# Error_Schematic.net
KiCad netlist of a schematic drawn in Altium Designer
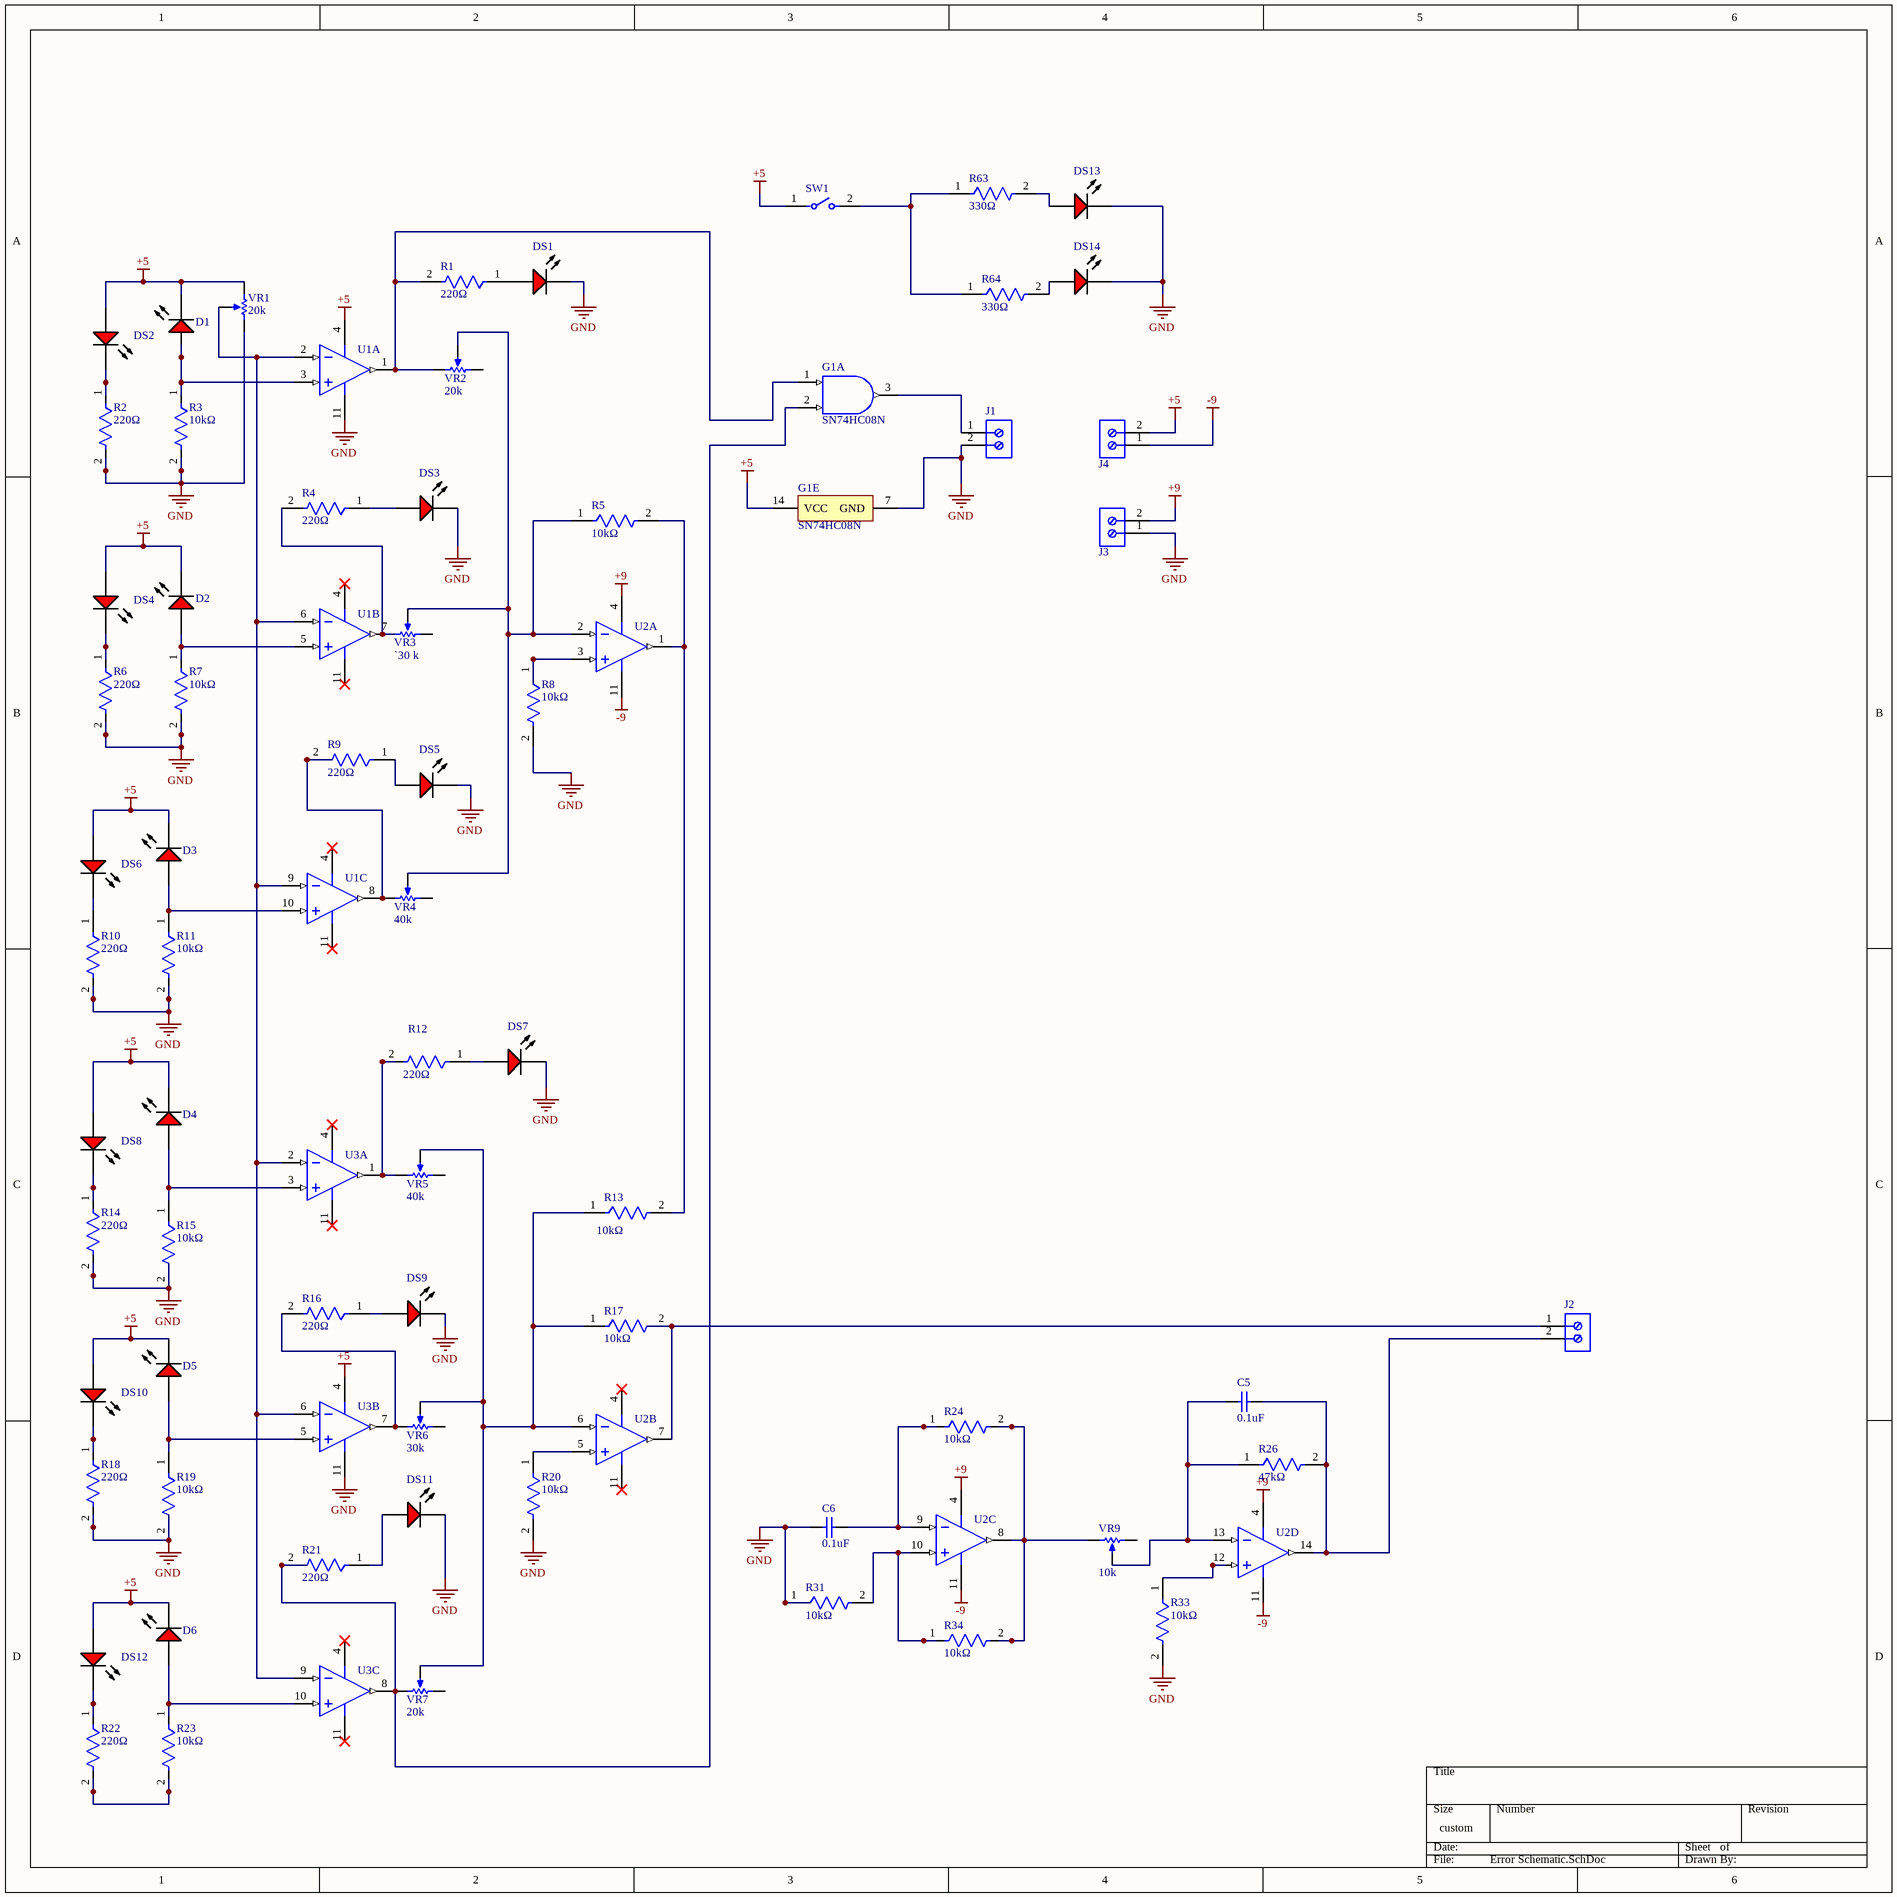
[diagram p0: Error Schematic.SchDoc]

(export (version "E")
  (design (tool "Eeschema 10.0.6"))
  (components
    (comp (ref "C5")
      (value "0.1uF")
      (footprint "CAPR51-254-508X318X736")
      (fields (field (name "Comment") "C320C104K5R5TA"))
      (libsource (lib "Altium Content Vault") (part "CAP-NP-2"))
    )
    (comp (ref "C6")
      (value "0.1uF")
      (footprint "CAPR51-254-508X318X736")
      (fields (field (name "Comment") "C320C104K5R5TA"))
      (libsource (lib "Altium Content Vault") (part "CAP-NP-2"))
    )
    (comp (ref "D1")
      (value "HLMP-3301")
      (footprint "AVAG-HLMP-3301-2")
      (description "T-1 3/4 (5 mm) Diffused LED Lamp, 1.9 V, -40 to 100 degC, 2-Pin THD, RoHS, Bulk")
      (fields (field (name "MANUFACTURER") "Avago"))
      (libsource (lib "Altium Content Vault") (part "LED-RED-K1A2-2"))
    )
    (comp (ref "D2")
      (value "HLMP-3301")
      (footprint "AVAG-HLMP-3301-2")
      (description "T-1 3/4 (5 mm) Diffused LED Lamp, 1.9 V, -40 to 100 degC, 2-Pin THD, RoHS, Bulk")
      (fields (field (name "MANUFACTURER") "Avago"))
      (libsource (lib "Altium Content Vault") (part "LED-RED-K1A2-2"))
    )
    (comp (ref "D3")
      (value "HLMP-3301")
      (footprint "AVAG-HLMP-3301-2")
      (description "T-1 3/4 (5 mm) Diffused LED Lamp, 1.9 V, -40 to 100 degC, 2-Pin THD, RoHS, Bulk")
      (fields (field (name "MANUFACTURER") "Avago"))
      (libsource (lib "Altium Content Vault") (part "LED-RED-K1A2-2"))
    )
    (comp (ref "D4")
      (value "HLMP-3301")
      (footprint "AVAG-HLMP-3301-2")
      (description "T-1 3/4 (5 mm) Diffused LED Lamp, 1.9 V, -40 to 100 degC, 2-Pin THD, RoHS, Bulk")
      (fields (field (name "MANUFACTURER") "Avago"))
      (libsource (lib "Altium Content Vault") (part "LED-RED-K1A2-2"))
    )
    (comp (ref "D5")
      (value "HLMP-3301")
      (footprint "AVAG-HLMP-3301-2")
      (description "T-1 3/4 (5 mm) Diffused LED Lamp, 1.9 V, -40 to 100 degC, 2-Pin THD, RoHS, Bulk")
      (fields (field (name "MANUFACTURER") "Avago"))
      (libsource (lib "Altium Content Vault") (part "LED-RED-K1A2-2"))
    )
    (comp (ref "D6")
      (value "HLMP-3301")
      (footprint "AVAG-HLMP-3301-2")
      (description "T-1 3/4 (5 mm) Diffused LED Lamp, 1.9 V, -40 to 100 degC, 2-Pin THD, RoHS, Bulk")
      (fields (field (name "MANUFACTURER") "Avago"))
      (libsource (lib "Altium Content Vault") (part "LED-RED-K1A2-2"))
    )
    (comp (ref "DS1")
      (value "HLMP-3301")
      (footprint "AVAG-HLMP-3301-2")
      (description "T-1 3/4 (5 mm) Diffused LED Lamp, 1.9 V, -40 to 100 degC, 2-Pin THD, RoHS, Bulk")
      (fields (field (name "MANUFACTURER") "Avago"))
      (libsource (lib "Altium Content Vault") (part "LED-RED-K1A2-2"))
    )
    (comp (ref "DS2")
      (value "HLMP-3301")
      (footprint "AVAG-HLMP-3301-2")
      (description "T-1 3/4 (5 mm) Diffused LED Lamp, 1.9 V, -40 to 100 degC, 2-Pin THD, RoHS, Bulk")
      (fields (field (name "MANUFACTURER") "Avago"))
      (libsource (lib "Altium Content Vault") (part "LED-RED-K1A2-2"))
    )
    (comp (ref "DS3")
      (value "HLMP-3301")
      (footprint "AVAG-HLMP-3301-2")
      (description "T-1 3/4 (5 mm) Diffused LED Lamp, 1.9 V, -40 to 100 degC, 2-Pin THD, RoHS, Bulk")
      (fields (field (name "MANUFACTURER") "Avago"))
      (libsource (lib "Altium Content Vault") (part "LED-RED-K1A2-2"))
    )
    (comp (ref "DS4")
      (value "HLMP-3301")
      (footprint "AVAG-HLMP-3301-2")
      (description "T-1 3/4 (5 mm) Diffused LED Lamp, 1.9 V, -40 to 100 degC, 2-Pin THD, RoHS, Bulk")
      (fields (field (name "MANUFACTURER") "Avago"))
      (libsource (lib "Altium Content Vault") (part "LED-RED-K1A2-2"))
    )
    (comp (ref "DS5")
      (value "HLMP-3301")
      (footprint "AVAG-HLMP-3301-2")
      (description "T-1 3/4 (5 mm) Diffused LED Lamp, 1.9 V, -40 to 100 degC, 2-Pin THD, RoHS, Bulk")
      (fields (field (name "MANUFACTURER") "Avago"))
      (libsource (lib "Altium Content Vault") (part "LED-RED-K1A2-2"))
    )
    (comp (ref "DS6")
      (value "HLMP-3301")
      (footprint "AVAG-HLMP-3301-2")
      (description "T-1 3/4 (5 mm) Diffused LED Lamp, 1.9 V, -40 to 100 degC, 2-Pin THD, RoHS, Bulk")
      (fields (field (name "MANUFACTURER") "Avago"))
      (libsource (lib "Altium Content Vault") (part "LED-RED-K1A2-2"))
    )
    (comp (ref "DS7")
      (value "HLMP-3301")
      (footprint "AVAG-HLMP-3301-2")
      (description "T-1 3/4 (5 mm) Diffused LED Lamp, 1.9 V, -40 to 100 degC, 2-Pin THD, RoHS, Bulk")
      (fields (field (name "MANUFACTURER") "Avago"))
      (libsource (lib "Altium Content Vault") (part "LED-RED-K1A2-2"))
    )
    (comp (ref "DS8")
      (value "HLMP-3301")
      (footprint "AVAG-HLMP-3301-2")
      (description "T-1 3/4 (5 mm) Diffused LED Lamp, 1.9 V, -40 to 100 degC, 2-Pin THD, RoHS, Bulk")
      (fields (field (name "MANUFACTURER") "Avago"))
      (libsource (lib "Altium Content Vault") (part "LED-RED-K1A2-2"))
    )
    (comp (ref "DS9")
      (value "HLMP-3301")
      (footprint "AVAG-HLMP-3301-2")
      (description "T-1 3/4 (5 mm) Diffused LED Lamp, 1.9 V, -40 to 100 degC, 2-Pin THD, RoHS, Bulk")
      (fields (field (name "MANUFACTURER") "Avago"))
      (libsource (lib "Altium Content Vault") (part "LED-RED-K1A2-2"))
    )
    (comp (ref "DS10")
      (value "HLMP-3301")
      (footprint "AVAG-HLMP-3301-2")
      (description "T-1 3/4 (5 mm) Diffused LED Lamp, 1.9 V, -40 to 100 degC, 2-Pin THD, RoHS, Bulk")
      (fields (field (name "MANUFACTURER") "Avago"))
      (libsource (lib "Altium Content Vault") (part "LED-RED-K1A2-2"))
    )
    (comp (ref "DS11")
      (value "HLMP-3301")
      (footprint "AVAG-HLMP-3301-2")
      (description "T-1 3/4 (5 mm) Diffused LED Lamp, 1.9 V, -40 to 100 degC, 2-Pin THD, RoHS, Bulk")
      (fields (field (name "MANUFACTURER") "Avago"))
      (libsource (lib "Altium Content Vault") (part "LED-RED-K1A2-2"))
    )
    (comp (ref "DS12")
      (value "HLMP-3301")
      (footprint "AVAG-HLMP-3301-2")
      (description "T-1 3/4 (5 mm) Diffused LED Lamp, 1.9 V, -40 to 100 degC, 2-Pin THD, RoHS, Bulk")
      (fields (field (name "MANUFACTURER") "Avago"))
      (libsource (lib "Altium Content Vault") (part "LED-RED-K1A2-2"))
    )
    (comp (ref "DS13")
      (value "HLMP-3301")
      (footprint "AVAG-HLMP-3301-2")
      (description "T-1 3/4 (5 mm) Diffused LED Lamp, 1.9 V, -40 to 100 degC, 2-Pin THD, RoHS, Bulk")
      (fields (field (name "MANUFACTURER") "Avago"))
      (libsource (lib "Altium Content Vault") (part "LED-RED-K1A2-2"))
    )
    (comp (ref "DS14")
      (value "HLMP-3301")
      (footprint "AVAG-HLMP-3301-2")
      (description "T-1 3/4 (5 mm) Diffused LED Lamp, 1.9 V, -40 to 100 degC, 2-Pin THD, RoHS, Bulk")
      (fields (field (name "MANUFACTURER") "Avago"))
      (libsource (lib "Altium Content Vault") (part "LED-RED-K1A2-2"))
    )
    (comp (ref "G1")
      (value "SN74HC08N")
      (footprint "N0014A")
      (description "Quadruple 2-Input Positive-AND Gates, N0014A, TUBE")
      (fields
        (field (name "GENERIC PART NUMBER") "SN74HC08")
        (field (name "MANUFACTURER") "Texas Instruments")
      )
      (libsource (lib "Altium Content Vault") (part "TI-AND-4-2IN-14"))
    )
    (comp (ref "J1")
      (value "691103110002")
      (footprint "691103110002")
      (description "Series 1031 - 3.50 mm Horizontal Entry Modular with Pressure Clamp WR-TBL, 2 pin")
      (fields (field (name "MANUFACTURER") "Wurth Elektronik") (field (name "PUBLISHER") "WurthElektronik"))
      (libsource (lib "Altium Content Vault") (part "WE-CN-1P-F-TB2"))
    )
    (comp (ref "J2")
      (value "691103110002")
      (footprint "691103110002")
      (description "Series 1031 - 3.50 mm Horizontal Entry Modular with Pressure Clamp WR-TBL, 2 pin")
      (fields (field (name "MANUFACTURER") "Wurth Elektronik") (field (name "PUBLISHER") "WurthElektronik"))
      (libsource (lib "Altium Content Vault") (part "WE-CN-1P-F-TB2"))
    )
    (comp (ref "J3")
      (value "691103110002")
      (footprint "691103110002")
      (description "Series 1031 - 3.50 mm Horizontal Entry Modular with Pressure Clamp WR-TBL, 2 pin")
      (fields (field (name "MANUFACTURER") "Wurth Elektronik") (field (name "PUBLISHER") "WurthElektronik"))
      (libsource (lib "Altium Content Vault") (part "WE-CN-1P-F-TB2"))
    )
    (comp (ref "J4")
      (value "691103110002")
      (footprint "691103110002")
      (description "Series 1031 - 3.50 mm Horizontal Entry Modular with Pressure Clamp WR-TBL, 2 pin")
      (fields (field (name "MANUFACTURER") "Wurth Elektronik") (field (name "PUBLISHER") "WurthElektronik"))
      (libsource (lib "Altium Content Vault") (part "WE-CN-1P-F-TB2"))
    )
    (comp (ref "R1")
      (value "MRS25000C1101FCT00")
      (footprint "FP-MRS25-MFG")
      (description "RES 1.1K OHM 0.6W 1% AXIAL")
      (fields
        (field (name "MANUFACTURER") "Vishay BC Components")
        (field (name "OCTOPART") "https://octopart.com/mrs25000c1101fct00-vishay-43740214")
        (field (name "RESISTANCE") "220Ω")
      )
      (libsource (lib "Altium Content Vault") (part "1029c3af85768c4190bb7ad29bc67b5"))
    )
    (comp (ref "R2")
      (value "MRS25000C1101FCT00")
      (footprint "FP-MRS25-MFG")
      (description "RES 1.1K OHM 0.6W 1% AXIAL")
      (fields
        (field (name "MANUFACTURER") "Vishay BC Components")
        (field (name "OCTOPART") "https://octopart.com/mrs25000c1101fct00-vishay-43740214")
        (field (name "RESISTANCE") "220Ω")
      )
      (libsource (lib "Altium Content Vault") (part "1029c3af85768c4190bb7ad29bc67b5"))
    )
    (comp (ref "R3")
      (value "MRS25000C1101FCT00")
      (footprint "FP-MRS25-MFG")
      (description "RES 1.1K OHM 0.6W 1% AXIAL")
      (fields
        (field (name "MANUFACTURER") "Vishay BC Components")
        (field (name "OCTOPART") "https://octopart.com/mrs25000c1101fct00-vishay-43740214")
        (field (name "RESISTANCE") "10kΩ")
      )
      (libsource (lib "Altium Content Vault") (part "1029c3af85768c4190bb7ad29bc67b5"))
    )
    (comp (ref "R4")
      (value "MRS25000C1101FCT00")
      (footprint "FP-MRS25-MFG")
      (description "RES 1.1K OHM 0.6W 1% AXIAL")
      (fields
        (field (name "MANUFACTURER") "Vishay BC Components")
        (field (name "OCTOPART") "https://octopart.com/mrs25000c1101fct00-vishay-43740214")
        (field (name "RESISTANCE") "220Ω")
      )
      (libsource (lib "Altium Content Vault") (part "1029c3af85768c4190bb7ad29bc67b5"))
    )
    (comp (ref "R5")
      (value "MRS25000C1101FCT00")
      (footprint "FP-MRS25-MFG")
      (description "RES 1.1K OHM 0.6W 1% AXIAL")
      (fields
        (field (name "MANUFACTURER") "Vishay BC Components")
        (field (name "OCTOPART") "https://octopart.com/mrs25000c1101fct00-vishay-43740214")
        (field (name "RESISTANCE") "10kΩ")
      )
      (libsource (lib "Altium Content Vault") (part "1029c3af85768c4190bb7ad29bc67b5"))
    )
    (comp (ref "R6")
      (value "MRS25000C1101FCT00")
      (footprint "FP-MRS25-MFG")
      (description "RES 1.1K OHM 0.6W 1% AXIAL")
      (fields
        (field (name "MANUFACTURER") "Vishay BC Components")
        (field (name "OCTOPART") "https://octopart.com/mrs25000c1101fct00-vishay-43740214")
        (field (name "RESISTANCE") "220Ω")
      )
      (libsource (lib "Altium Content Vault") (part "1029c3af85768c4190bb7ad29bc67b5"))
    )
    (comp (ref "R7")
      (value "MRS25000C1101FCT00")
      (footprint "FP-MRS25-MFG")
      (description "RES 1.1K OHM 0.6W 1% AXIAL")
      (fields
        (field (name "MANUFACTURER") "Vishay BC Components")
        (field (name "OCTOPART") "https://octopart.com/mrs25000c1101fct00-vishay-43740214")
        (field (name "RESISTANCE") "10kΩ")
      )
      (libsource (lib "Altium Content Vault") (part "1029c3af85768c4190bb7ad29bc67b5"))
    )
    (comp (ref "R8")
      (value "MRS25000C1101FCT00")
      (footprint "FP-MRS25-MFG")
      (description "RES 1.1K OHM 0.6W 1% AXIAL")
      (fields
        (field (name "MANUFACTURER") "Vishay BC Components")
        (field (name "OCTOPART") "https://octopart.com/mrs25000c1101fct00-vishay-43740214")
        (field (name "RESISTANCE") "10kΩ")
      )
      (libsource (lib "Altium Content Vault") (part "1029c3af85768c4190bb7ad29bc67b5"))
    )
    (comp (ref "R9")
      (value "MRS25000C1101FCT00")
      (footprint "FP-MRS25-MFG")
      (description "RES 1.1K OHM 0.6W 1% AXIAL")
      (fields
        (field (name "MANUFACTURER") "Vishay BC Components")
        (field (name "OCTOPART") "https://octopart.com/mrs25000c1101fct00-vishay-43740214")
        (field (name "RESISTANCE") "220Ω")
      )
      (libsource (lib "Altium Content Vault") (part "1029c3af85768c4190bb7ad29bc67b5"))
    )
    (comp (ref "R10")
      (value "MRS25000C1101FCT00")
      (footprint "FP-MRS25-MFG")
      (description "RES 1.1K OHM 0.6W 1% AXIAL")
      (fields
        (field (name "MANUFACTURER") "Vishay BC Components")
        (field (name "OCTOPART") "https://octopart.com/mrs25000c1101fct00-vishay-43740214")
        (field (name "RESISTANCE") "220Ω")
      )
      (libsource (lib "Altium Content Vault") (part "1029c3af85768c4190bb7ad29bc67b5"))
    )
    (comp (ref "R11")
      (value "MRS25000C1101FCT00")
      (footprint "FP-MRS25-MFG")
      (description "RES 1.1K OHM 0.6W 1% AXIAL")
      (fields
        (field (name "MANUFACTURER") "Vishay BC Components")
        (field (name "OCTOPART") "https://octopart.com/mrs25000c1101fct00-vishay-43740214")
        (field (name "RESISTANCE") "10kΩ")
      )
      (libsource (lib "Altium Content Vault") (part "1029c3af85768c4190bb7ad29bc67b5"))
    )
    (comp (ref "R12")
      (value "MRS25000C1101FCT00")
      (footprint "FP-MRS25-MFG")
      (description "RES 1.1K OHM 0.6W 1% AXIAL")
      (fields
        (field (name "MANUFACTURER") "Vishay BC Components")
        (field (name "OCTOPART") "https://octopart.com/mrs25000c1101fct00-vishay-43740214")
        (field (name "RESISTANCE") "220Ω")
      )
      (libsource (lib "Altium Content Vault") (part "1029c3af85768c4190bb7ad29bc67b5"))
    )
    (comp (ref "R13")
      (value "MRS25000C1101FCT00")
      (footprint "FP-MRS25-MFG")
      (description "RES 1.1K OHM 0.6W 1% AXIAL")
      (fields
        (field (name "MANUFACTURER") "Vishay BC Components")
        (field (name "OCTOPART") "https://octopart.com/mrs25000c1101fct00-vishay-43740214")
        (field (name "RESISTANCE") "10kΩ")
      )
      (libsource (lib "Altium Content Vault") (part "1029c3af85768c4190bb7ad29bc67b5"))
    )
    (comp (ref "R14")
      (value "MRS25000C1101FCT00")
      (footprint "FP-MRS25-MFG")
      (description "RES 1.1K OHM 0.6W 1% AXIAL")
      (fields
        (field (name "MANUFACTURER") "Vishay BC Components")
        (field (name "OCTOPART") "https://octopart.com/mrs25000c1101fct00-vishay-43740214")
        (field (name "RESISTANCE") "220Ω")
      )
      (libsource (lib "Altium Content Vault") (part "1029c3af85768c4190bb7ad29bc67b5"))
    )
    (comp (ref "R15")
      (value "MRS25000C1101FCT00")
      (footprint "FP-MRS25-MFG")
      (description "RES 1.1K OHM 0.6W 1% AXIAL")
      (fields
        (field (name "MANUFACTURER") "Vishay BC Components")
        (field (name "OCTOPART") "https://octopart.com/mrs25000c1101fct00-vishay-43740214")
        (field (name "RESISTANCE") "10kΩ")
      )
      (libsource (lib "Altium Content Vault") (part "1029c3af85768c4190bb7ad29bc67b5"))
    )
    (comp (ref "R16")
      (value "MRS25000C1101FCT00")
      (footprint "FP-MRS25-MFG")
      (description "RES 1.1K OHM 0.6W 1% AXIAL")
      (fields
        (field (name "MANUFACTURER") "Vishay BC Components")
        (field (name "OCTOPART") "https://octopart.com/mrs25000c1101fct00-vishay-43740214")
        (field (name "RESISTANCE") "220Ω")
      )
      (libsource (lib "Altium Content Vault") (part "1029c3af85768c4190bb7ad29bc67b5"))
    )
    (comp (ref "R17")
      (value "MRS25000C1101FCT00")
      (footprint "FP-MRS25-MFG")
      (description "RES 1.1K OHM 0.6W 1% AXIAL")
      (fields
        (field (name "MANUFACTURER") "Vishay BC Components")
        (field (name "OCTOPART") "https://octopart.com/mrs25000c1101fct00-vishay-43740214")
        (field (name "RESISTANCE") "10kΩ")
      )
      (libsource (lib "Altium Content Vault") (part "1029c3af85768c4190bb7ad29bc67b5"))
    )
    (comp (ref "R18")
      (value "MRS25000C1101FCT00")
      (footprint "FP-MRS25-MFG")
      (description "RES 1.1K OHM 0.6W 1% AXIAL")
      (fields
        (field (name "MANUFACTURER") "Vishay BC Components")
        (field (name "OCTOPART") "https://octopart.com/mrs25000c1101fct00-vishay-43740214")
        (field (name "RESISTANCE") "220Ω")
      )
      (libsource (lib "Altium Content Vault") (part "1029c3af85768c4190bb7ad29bc67b5"))
    )
    (comp (ref "R19")
      (value "MRS25000C1101FCT00")
      (footprint "FP-MRS25-MFG")
      (description "RES 1.1K OHM 0.6W 1% AXIAL")
      (fields
        (field (name "MANUFACTURER") "Vishay BC Components")
        (field (name "OCTOPART") "https://octopart.com/mrs25000c1101fct00-vishay-43740214")
        (field (name "RESISTANCE") "10kΩ")
      )
      (libsource (lib "Altium Content Vault") (part "1029c3af85768c4190bb7ad29bc67b5"))
    )
    (comp (ref "R20")
      (value "MRS25000C1101FCT00")
      (footprint "FP-MRS25-MFG")
      (description "RES 1.1K OHM 0.6W 1% AXIAL")
      (fields
        (field (name "MANUFACTURER") "Vishay BC Components")
        (field (name "OCTOPART") "https://octopart.com/mrs25000c1101fct00-vishay-43740214")
        (field (name "RESISTANCE") "10kΩ")
      )
      (libsource (lib "Altium Content Vault") (part "1029c3af85768c4190bb7ad29bc67b5"))
    )
    (comp (ref "R21")
      (value "MRS25000C1101FCT00")
      (footprint "FP-MRS25-MFG")
      (description "RES 1.1K OHM 0.6W 1% AXIAL")
      (fields
        (field (name "MANUFACTURER") "Vishay BC Components")
        (field (name "OCTOPART") "https://octopart.com/mrs25000c1101fct00-vishay-43740214")
        (field (name "RESISTANCE") "220Ω")
      )
      (libsource (lib "Altium Content Vault") (part "1029c3af85768c4190bb7ad29bc67b5"))
    )
    (comp (ref "R22")
      (value "MRS25000C1101FCT00")
      (footprint "FP-MRS25-MFG")
      (description "RES 1.1K OHM 0.6W 1% AXIAL")
      (fields
        (field (name "MANUFACTURER") "Vishay BC Components")
        (field (name "OCTOPART") "https://octopart.com/mrs25000c1101fct00-vishay-43740214")
        (field (name "RESISTANCE") "220Ω")
      )
      (libsource (lib "Altium Content Vault") (part "1029c3af85768c4190bb7ad29bc67b5"))
    )
    (comp (ref "R23")
      (value "MRS25000C1101FCT00")
      (footprint "FP-MRS25-MFG")
      (description "RES 1.1K OHM 0.6W 1% AXIAL")
      (fields
        (field (name "MANUFACTURER") "Vishay BC Components")
        (field (name "OCTOPART") "https://octopart.com/mrs25000c1101fct00-vishay-43740214")
        (field (name "RESISTANCE") "10kΩ")
      )
      (libsource (lib "Altium Content Vault") (part "1029c3af85768c4190bb7ad29bc67b5"))
    )
    (comp (ref "R24")
      (value "MRS25000C1101FCT00")
      (footprint "FP-MRS25-MFG")
      (description "RES 1.1K OHM 0.6W 1% AXIAL")
      (fields
        (field (name "MANUFACTURER") "Vishay BC Components")
        (field (name "OCTOPART") "https://octopart.com/mrs25000c1101fct00-vishay-43740214")
        (field (name "RESISTANCE") "10kΩ")
      )
      (libsource (lib "Altium Content Vault") (part "1029c3af85768c4190bb7ad29bc67b5"))
    )
    (comp (ref "R26")
      (value "MRS25000C1101FCT00")
      (footprint "FP-MRS25-MFG")
      (description "RES 1.1K OHM 0.6W 1% AXIAL")
      (fields
        (field (name "MANUFACTURER") "Vishay BC Components")
        (field (name "OCTOPART") "https://octopart.com/mrs25000c1101fct00-vishay-43740214")
        (field (name "RESISTANCE") "47kΩ")
      )
      (libsource (lib "Altium Content Vault") (part "1029c3af85768c4190bb7ad29bc67b5"))
    )
    (comp (ref "R31")
      (value "MRS25000C1101FCT00")
      (footprint "FP-MRS25-MFG")
      (description "RES 1.1K OHM 0.6W 1% AXIAL")
      (fields
        (field (name "MANUFACTURER") "Vishay BC Components")
        (field (name "OCTOPART") "https://octopart.com/mrs25000c1101fct00-vishay-43740214")
        (field (name "RESISTANCE") "10kΩ")
      )
      (libsource (lib "Altium Content Vault") (part "1029c3af85768c4190bb7ad29bc67b5"))
    )
    (comp (ref "R33")
      (value "MRS25000C1101FCT00")
      (footprint "FP-MRS25-MFG")
      (description "RES 1.1K OHM 0.6W 1% AXIAL")
      (fields
        (field (name "MANUFACTURER") "Vishay BC Components")
        (field (name "OCTOPART") "https://octopart.com/mrs25000c1101fct00-vishay-43740214")
        (field (name "RESISTANCE") "10kΩ")
      )
      (libsource (lib "Altium Content Vault") (part "1029c3af85768c4190bb7ad29bc67b5"))
    )
    (comp (ref "R34")
      (value "MRS25000C1101FCT00")
      (footprint "FP-MRS25-MFG")
      (description "RES 1.1K OHM 0.6W 1% AXIAL")
      (fields
        (field (name "MANUFACTURER") "Vishay BC Components")
        (field (name "OCTOPART") "https://octopart.com/mrs25000c1101fct00-vishay-43740214")
        (field (name "RESISTANCE") "10kΩ")
      )
      (libsource (lib "Altium Content Vault") (part "1029c3af85768c4190bb7ad29bc67b5"))
    )
    (comp (ref "R63")
      (value "MRS25000C1101FCT00")
      (footprint "FP-MRS25-MFG")
      (description "RES 1.1K OHM 0.6W 1% AXIAL")
      (fields
        (field (name "MANUFACTURER") "Vishay BC Components")
        (field (name "OCTOPART") "https://octopart.com/mrs25000c1101fct00-vishay-43740214")
        (field (name "RESISTANCE") "330Ω")
      )
      (libsource (lib "Altium Content Vault") (part "1029c3af85768c4190bb7ad29bc67b5"))
    )
    (comp (ref "R64")
      (value "MRS25000C1101FCT00")
      (footprint "FP-MRS25-MFG")
      (description "RES 1.1K OHM 0.6W 1% AXIAL")
      (fields
        (field (name "MANUFACTURER") "Vishay BC Components")
        (field (name "OCTOPART") "https://octopart.com/mrs25000c1101fct00-vishay-43740214")
        (field (name "RESISTANCE") "330Ω")
      )
      (libsource (lib "Altium Content Vault") (part "1029c3af85768c4190bb7ad29bc67b5"))
    )
    (comp (ref "SW1")
      (value "BD01")
      (footprint "FP-BD01-MFG")
      (description "SWITCH SLIDE DIP SPST 100MA 5V")
      (libsource (lib "Altium Content Vault") (part "bb27bde45df87f1f469753f287ef5ae"))
    )
    (comp (ref "U1")
      (value "LM324N")
      (footprint "N0014A")
      (description "Low Power Quad Operational Amplifier, 14-pin MDIP")
      (fields (field (name "MANUFACTURER") "Texas Instruments"))
      (libsource (lib "Altium Content Vault") (part "AMP-OPA-LM124-14"))
    )
    (comp (ref "U2")
      (value "LM324N")
      (footprint "N0014A")
      (description "Low Power Quad Operational Amplifier, 14-pin MDIP")
      (fields (field (name "MANUFACTURER") "Texas Instruments"))
      (libsource (lib "Altium Content Vault") (part "AMP-OPA-LM124-14"))
    )
    (comp (ref "U3")
      (value "LM324N")
      (footprint "N0014A")
      (description "Low Power Quad Operational Amplifier, 14-pin MDIP")
      (fields (field (name "MANUFACTURER") "Texas Instruments"))
      (libsource (lib "Altium Content Vault") (part "AMP-OPA-LM124-14"))
    )
    (comp (ref "VR1")
      (value "3296W-1-103LF")
      (footprint "BOUR-3296W")
      (fields (field (name "RESISTANCE") "20k") (field (name "TOLERANCE") "1%"))
      (libsource (lib "Altium Content Vault") (part "RES-POT-3"))
    )
    (comp (ref "VR2")
      (value "3296W-1-103LF")
      (footprint "BOUR-3296W")
      (fields (field (name "RESISTANCE") "20k") (field (name "TOLERANCE") "1%"))
      (libsource (lib "Altium Content Vault") (part "RES-POT-3"))
    )
    (comp (ref "VR3")
      (value "3296W-1-103LF")
      (footprint "BOUR-3296W")
      (fields (field (name "RESISTANCE") "`30 k") (field (name "TOLERANCE") "1%"))
      (libsource (lib "Altium Content Vault") (part "RES-POT-3"))
    )
    (comp (ref "VR4")
      (value "3296W-1-103LF")
      (footprint "BOUR-3296W")
      (fields (field (name "RESISTANCE") "40k") (field (name "TOLERANCE") "1%"))
      (libsource (lib "Altium Content Vault") (part "RES-POT-3"))
    )
    (comp (ref "VR5")
      (value "3296W-1-103LF")
      (footprint "BOUR-3296W")
      (fields (field (name "RESISTANCE") "40k") (field (name "TOLERANCE") "1%"))
      (libsource (lib "Altium Content Vault") (part "RES-POT-3"))
    )
    (comp (ref "VR6")
      (value "3296W-1-103LF")
      (footprint "BOUR-3296W")
      (fields (field (name "RESISTANCE") "30k") (field (name "TOLERANCE") "1%"))
      (libsource (lib "Altium Content Vault") (part "RES-POT-3"))
    )
    (comp (ref "VR7")
      (value "3296W-1-103LF")
      (footprint "BOUR-3296W")
      (fields (field (name "RESISTANCE") "20k") (field (name "TOLERANCE") "1%"))
      (libsource (lib "Altium Content Vault") (part "RES-POT-3"))
    )
    (comp (ref "VR9")
      (value "3296W-1-103LF")
      (footprint "BOUR-3296W")
      (fields (field (name "RESISTANCE") "10k") (field (name "TOLERANCE") "1%"))
      (libsource (lib "Altium Content Vault") (part "RES-POT-3"))
    )
  )
  (nets
    (net (code "1") (name "+5") (class "Default")
      (node (ref "D1") (pin "1") (pinfunction "K_1") (pintype "passive"))
      (node (ref "D2") (pin "1") (pinfunction "K_1") (pintype "passive"))
      (node (ref "D3") (pin "1") (pinfunction "K_1") (pintype "passive"))
      (node (ref "D4") (pin "1") (pinfunction "K_1") (pintype "passive"))
      (node (ref "D5") (pin "1") (pinfunction "K_1") (pintype "passive"))
      (node (ref "D6") (pin "1") (pinfunction "K_1") (pintype "passive"))
      (node (ref "DS10") (pin "2") (pinfunction "A_2") (pintype "passive"))
      (node (ref "DS12") (pin "2") (pinfunction "A_2") (pintype "passive"))
      (node (ref "DS2") (pin "2") (pinfunction "A_2") (pintype "passive"))
      (node (ref "DS4") (pin "2") (pinfunction "A_2") (pintype "passive"))
      (node (ref "DS6") (pin "2") (pinfunction "A_2") (pintype "passive"))
      (node (ref "DS8") (pin "2") (pinfunction "A_2") (pintype "passive"))
      (node (ref "G1") (pin "14") (pinfunction "VCC_14") (pintype "power_in"))
      (node (ref "J4") (pin "2") (pinfunction "2_2") (pintype "passive"))
      (node (ref "SW1") (pin "1") (pinfunction "1_1") (pintype "passive"))
      (node (ref "U1") (pin "4") (pinfunction "V+_4") (pintype "power_in"))
      (node (ref "U3") (pin "4") (pinfunction "V+_4") (pintype "power_in"))
      (node (ref "VR1") (pin "1") (pinfunction "CCW_1") (pintype "passive"))
    )
    (net (code "2") (name "+9") (class "Default")
      (node (ref "J3") (pin "2") (pinfunction "2_2") (pintype "passive"))
      (node (ref "U2") (pin "4") (pinfunction "V+_4") (pintype "power_in"))
    )
    (net (code "3") (name "-9") (class "Default")
      (node (ref "J4") (pin "1") (pinfunction "1_1") (pintype "passive"))
      (node (ref "U2") (pin "11") (pinfunction "GND_11") (pintype "power_in"))
    )
    (net (code "4") (name "GND") (class "Default")
      (node (ref "C6") (pin "1") (pinfunction "1_1") (pintype "passive"))
      (node (ref "DS1") (pin "1") (pinfunction "K_1") (pintype "passive"))
      (node (ref "DS11") (pin "1") (pinfunction "K_1") (pintype "passive"))
      (node (ref "DS13") (pin "1") (pinfunction "K_1") (pintype "passive"))
      (node (ref "DS14") (pin "1") (pinfunction "K_1") (pintype "passive"))
      (node (ref "DS3") (pin "1") (pinfunction "K_1") (pintype "passive"))
      (node (ref "DS5") (pin "1") (pinfunction "K_1") (pintype "passive"))
      (node (ref "DS7") (pin "1") (pinfunction "K_1") (pintype "passive"))
      (node (ref "DS9") (pin "1") (pinfunction "K_1") (pintype "passive"))
      (node (ref "G1") (pin "7") (pinfunction "GND_7") (pintype "power_in"))
      (node (ref "J1") (pin "2") (pinfunction "2_2") (pintype "passive"))
      (node (ref "J3") (pin "1") (pinfunction "1_1") (pintype "passive"))
      (node (ref "R10") (pin "2") (pinfunction "2_2") (pintype "passive"))
      (node (ref "R11") (pin "2") (pinfunction "2_2") (pintype "passive"))
      (node (ref "R14") (pin "2") (pinfunction "2_2") (pintype "passive"))
      (node (ref "R15") (pin "2") (pinfunction "2_2") (pintype "passive"))
      (node (ref "R18") (pin "2") (pinfunction "2_2") (pintype "passive"))
      (node (ref "R19") (pin "2") (pinfunction "2_2") (pintype "passive"))
      (node (ref "R2") (pin "2") (pinfunction "2_2") (pintype "passive"))
      (node (ref "R20") (pin "2") (pinfunction "2_2") (pintype "passive"))
      (node (ref "R3") (pin "2") (pinfunction "2_2") (pintype "passive"))
      (node (ref "R31") (pin "1") (pinfunction "1_1") (pintype "passive"))
      (node (ref "R33") (pin "2") (pinfunction "2_2") (pintype "passive"))
      (node (ref "R6") (pin "2") (pinfunction "2_2") (pintype "passive"))
      (node (ref "R7") (pin "2") (pinfunction "2_2") (pintype "passive"))
      (node (ref "R8") (pin "2") (pinfunction "2_2") (pintype "passive"))
      (node (ref "U1") (pin "11") (pinfunction "GND_11") (pintype "power_in"))
      (node (ref "U3") (pin "11") (pinfunction "GND_11") (pintype "power_in"))
      (node (ref "VR1") (pin "3") (pinfunction "CW_3") (pintype "passive"))
    )
    (net (code "5") (name "Net-(D1-A)") (class "Default")
      (node (ref "D1") (pin "2") (pinfunction "A_2") (pintype "passive"))
      (node (ref "R3") (pin "1") (pinfunction "1_1") (pintype "passive"))
      (node (ref "U1") (pin "3") (pinfunction "IN1+_3") (pintype "input"))
    )
    (net (code "6") (name "Net-(D2-A)") (class "Default")
      (node (ref "D2") (pin "2") (pinfunction "A_2") (pintype "passive"))
      (node (ref "R7") (pin "1") (pinfunction "1_1") (pintype "passive"))
      (node (ref "U1") (pin "5") (pinfunction "IN2+_5") (pintype "input"))
    )
    (net (code "7") (name "Net-(D3-A)") (class "Default")
      (node (ref "D3") (pin "2") (pinfunction "A_2") (pintype "passive"))
      (node (ref "R11") (pin "1") (pinfunction "1_1") (pintype "passive"))
      (node (ref "U1") (pin "10") (pinfunction "IN3+_10") (pintype "input"))
    )
    (net (code "8") (name "Net-(D4-A)") (class "Default")
      (node (ref "D4") (pin "2") (pinfunction "A_2") (pintype "passive"))
      (node (ref "R15") (pin "1") (pinfunction "1_1") (pintype "passive"))
      (node (ref "U3") (pin "3") (pinfunction "IN1+_3") (pintype "input"))
    )
    (net (code "9") (name "Net-(D5-A)") (class "Default")
      (node (ref "D5") (pin "2") (pinfunction "A_2") (pintype "passive"))
      (node (ref "R19") (pin "1") (pinfunction "1_1") (pintype "passive"))
      (node (ref "U3") (pin "5") (pinfunction "IN2+_5") (pintype "input"))
    )
    (net (code "10") (name "Net-(D6-A)") (class "Default")
      (node (ref "D6") (pin "2") (pinfunction "A_2") (pintype "passive"))
      (node (ref "R23") (pin "1") (pinfunction "1_1") (pintype "passive"))
      (node (ref "U3") (pin "10") (pinfunction "IN3+_10") (pintype "input"))
    )
    (net (code "11") (name "Net-(DS1-A)") (class "Default")
      (node (ref "DS1") (pin "2") (pinfunction "A_2") (pintype "passive"))
      (node (ref "R1") (pin "1") (pinfunction "1_1") (pintype "passive"))
    )
    (net (code "12") (name "Net-(DS2-K)") (class "Default")
      (node (ref "DS2") (pin "1") (pinfunction "K_1") (pintype "passive"))
      (node (ref "R2") (pin "1") (pinfunction "1_1") (pintype "passive"))
    )
    (net (code "13") (name "Net-(DS3-A)") (class "Default")
      (node (ref "DS3") (pin "2") (pinfunction "A_2") (pintype "passive"))
      (node (ref "R4") (pin "1") (pinfunction "1_1") (pintype "passive"))
    )
    (net (code "14") (name "Net-(DS4-K)") (class "Default")
      (node (ref "DS4") (pin "1") (pinfunction "K_1") (pintype "passive"))
      (node (ref "R6") (pin "1") (pinfunction "1_1") (pintype "passive"))
    )
    (net (code "15") (name "Net-(DS5-A)") (class "Default")
      (node (ref "DS5") (pin "2") (pinfunction "A_2") (pintype "passive"))
      (node (ref "R9") (pin "1") (pinfunction "1_1") (pintype "passive"))
    )
    (net (code "16") (name "Net-(DS6-K)") (class "Default")
      (node (ref "DS6") (pin "1") (pinfunction "K_1") (pintype "passive"))
      (node (ref "R10") (pin "1") (pinfunction "1_1") (pintype "passive"))
    )
    (net (code "17") (name "Net-(DS7-A)") (class "Default")
      (node (ref "DS7") (pin "2") (pinfunction "A_2") (pintype "passive"))
      (node (ref "R12") (pin "1") (pinfunction "1_1") (pintype "passive"))
    )
    (net (code "18") (name "Net-(DS8-K)") (class "Default")
      (node (ref "DS8") (pin "1") (pinfunction "K_1") (pintype "passive"))
      (node (ref "R14") (pin "1") (pinfunction "1_1") (pintype "passive"))
    )
    (net (code "19") (name "Net-(DS9-A)") (class "Default")
      (node (ref "DS9") (pin "2") (pinfunction "A_2") (pintype "passive"))
      (node (ref "R16") (pin "1") (pinfunction "1_1") (pintype "passive"))
    )
    (net (code "20") (name "Net-(DS10-K)") (class "Default")
      (node (ref "DS10") (pin "1") (pinfunction "K_1") (pintype "passive"))
      (node (ref "R18") (pin "1") (pinfunction "1_1") (pintype "passive"))
    )
    (net (code "21") (name "Net-(DS11-A)") (class "Default")
      (node (ref "DS11") (pin "2") (pinfunction "A_2") (pintype "passive"))
      (node (ref "R21") (pin "1") (pinfunction "1_1") (pintype "passive"))
    )
    (net (code "22") (name "Net-(DS12-K)") (class "Default")
      (node (ref "DS12") (pin "1") (pinfunction "K_1") (pintype "passive"))
      (node (ref "R22") (pin "1") (pinfunction "1_1") (pintype "passive"))
    )
    (net (code "23") (name "Net-(DS13-A)") (class "Default")
      (node (ref "DS13") (pin "2") (pinfunction "A_2") (pintype "passive"))
      (node (ref "R63") (pin "2") (pinfunction "2_2") (pintype "passive"))
    )
    (net (code "24") (name "Net-(DS14-A)") (class "Default")
      (node (ref "DS14") (pin "2") (pinfunction "A_2") (pintype "passive"))
      (node (ref "R64") (pin "2") (pinfunction "2_2") (pintype "passive"))
    )
    (net (code "25") (name "Net-(G1A-1A)") (class "Default")
      (node (ref "G1") (pin "1") (pinfunction "1A_1") (pintype "input"))
      (node (ref "R1") (pin "2") (pinfunction "2_2") (pintype "passive"))
      (node (ref "U1") (pin "1") (pinfunction "OUT1_1") (pintype "output"))
      (node (ref "VR2") (pin "3") (pinfunction "CW_3") (pintype "passive"))
    )
    (net (code "26") (name "Net-(G1A-1B)") (class "Default")
      (node (ref "G1") (pin "2") (pinfunction "1B_2") (pintype "input"))
      (node (ref "R21") (pin "2") (pinfunction "2_2") (pintype "passive"))
      (node (ref "U3") (pin "8") (pinfunction "OUT3_8") (pintype "output"))
      (node (ref "VR7") (pin "3") (pinfunction "CW_3") (pintype "passive"))
    )
    (net (code "27") (name "Net-(G1A-1Y)") (class "Default")
      (node (ref "G1") (pin "3") (pinfunction "1Y_3") (pintype "output"))
      (node (ref "J1") (pin "1") (pinfunction "1_1") (pintype "passive"))
    )
    (net (code "28") (name "Net-(R22-Pad2)") (class "Default")
      (node (ref "R22") (pin "2") (pinfunction "2_2") (pintype "passive"))
      (node (ref "R23") (pin "2") (pinfunction "2_2") (pintype "passive"))
    )
    (net (code "29") (name "Net-(R63-Pad1)") (class "Default")
      (node (ref "R63") (pin "1") (pinfunction "1_1") (pintype "passive"))
      (node (ref "R64") (pin "1") (pinfunction "1_1") (pintype "passive"))
      (node (ref "SW1") (pin "2") (pinfunction "2_2") (pintype "passive"))
    )
    (net (code "30") (name "Net-(U1A-IN1-)") (class "Default")
      (node (ref "U1") (pin "2") (pinfunction "IN1-_2") (pintype "input"))
      (node (ref "U1") (pin "6") (pinfunction "IN2-_6") (pintype "input"))
      (node (ref "U1") (pin "9") (pinfunction "IN3-_9") (pintype "input"))
      (node (ref "U3") (pin "2") (pinfunction "IN1-_2") (pintype "input"))
      (node (ref "U3") (pin "6") (pinfunction "IN2-_6") (pintype "input"))
      (node (ref "U3") (pin "9") (pinfunction "IN3-_9") (pintype "input"))
      (node (ref "VR1") (pin "2") (pinfunction "S_2") (pintype "passive"))
    )
    (net (code "31") (name "Net-(U1B-OUT2)") (class "Default")
      (node (ref "R4") (pin "2") (pinfunction "2_2") (pintype "passive"))
      (node (ref "U1") (pin "7") (pinfunction "OUT2_7") (pintype "output"))
      (node (ref "VR3") (pin "3") (pinfunction "CW_3") (pintype "passive"))
    )
    (net (code "32") (name "Net-(U1C-OUT3)") (class "Default")
      (node (ref "R9") (pin "2") (pinfunction "2_2") (pintype "passive"))
      (node (ref "U1") (pin "8") (pinfunction "OUT3_8") (pintype "output"))
      (node (ref "VR4") (pin "3") (pinfunction "CW_3") (pintype "passive"))
    )
    (net (code "33") (name "Net-(U2A-IN1+)") (class "Default")
      (node (ref "R8") (pin "1") (pinfunction "1_1") (pintype "passive"))
      (node (ref "U2") (pin "3") (pinfunction "IN1+_3") (pintype "input"))
    )
    (net (code "34") (name "Net-(U2A-IN1-)") (class "Default")
      (node (ref "R5") (pin "1") (pinfunction "1_1") (pintype "passive"))
      (node (ref "U2") (pin "2") (pinfunction "IN1-_2") (pintype "input"))
      (node (ref "VR2") (pin "2") (pinfunction "S_2") (pintype "passive"))
      (node (ref "VR3") (pin "2") (pinfunction "S_2") (pintype "passive"))
      (node (ref "VR4") (pin "2") (pinfunction "S_2") (pintype "passive"))
    )
    (net (code "35") (name "Net-(U2A-OUT1)") (class "Default")
      (node (ref "R13") (pin "2") (pinfunction "2_2") (pintype "passive"))
      (node (ref "R5") (pin "2") (pinfunction "2_2") (pintype "passive"))
      (node (ref "U2") (pin "1") (pinfunction "OUT1_1") (pintype "output"))
    )
    (net (code "36") (name "Net-(U2B-IN2+)") (class "Default")
      (node (ref "R20") (pin "1") (pinfunction "1_1") (pintype "passive"))
      (node (ref "U2") (pin "5") (pinfunction "IN2+_5") (pintype "input"))
    )
    (net (code "37") (name "Net-(U2B-IN2-)") (class "Default")
      (node (ref "R13") (pin "1") (pinfunction "1_1") (pintype "passive"))
      (node (ref "R17") (pin "1") (pinfunction "1_1") (pintype "passive"))
      (node (ref "U2") (pin "6") (pinfunction "IN2-_6") (pintype "input"))
      (node (ref "VR5") (pin "2") (pinfunction "S_2") (pintype "passive"))
      (node (ref "VR6") (pin "2") (pinfunction "S_2") (pintype "passive"))
      (node (ref "VR7") (pin "2") (pinfunction "S_2") (pintype "passive"))
    )
    (net (code "38") (name "Net-(U2B-OUT2)") (class "Default")
      (node (ref "J2") (pin "1") (pinfunction "1_1") (pintype "passive"))
      (node (ref "R17") (pin "2") (pinfunction "2_2") (pintype "passive"))
      (node (ref "U2") (pin "7") (pinfunction "OUT2_7") (pintype "output"))
    )
    (net (code "39") (name "Net-(U2C-IN3+)") (class "Default")
      (node (ref "R31") (pin "2") (pinfunction "2_2") (pintype "passive"))
      (node (ref "R34") (pin "1") (pinfunction "1_1") (pintype "passive"))
      (node (ref "U2") (pin "10") (pinfunction "IN3+_10") (pintype "input"))
    )
    (net (code "40") (name "Net-(U2C-IN3-)") (class "Default")
      (node (ref "C6") (pin "2") (pinfunction "2_2") (pintype "passive"))
      (node (ref "R24") (pin "1") (pinfunction "1_1") (pintype "passive"))
      (node (ref "U2") (pin "9") (pinfunction "IN3-_9") (pintype "input"))
    )
    (net (code "41") (name "Net-(U2C-OUT3)") (class "Default")
      (node (ref "R24") (pin "2") (pinfunction "2_2") (pintype "passive"))
      (node (ref "R34") (pin "2") (pinfunction "2_2") (pintype "passive"))
      (node (ref "U2") (pin "8") (pinfunction "OUT3_8") (pintype "output"))
      (node (ref "VR9") (pin "1") (pinfunction "CCW_1") (pintype "passive"))
    )
    (net (code "42") (name "Net-(U2D-IN4+)") (class "Default")
      (node (ref "R33") (pin "1") (pinfunction "1_1") (pintype "passive"))
      (node (ref "U2") (pin "12") (pinfunction "IN4+_12") (pintype "input"))
    )
    (net (code "43") (name "Net-(U2D-IN4-)") (class "Default")
      (node (ref "C5") (pin "1") (pinfunction "1_1") (pintype "passive"))
      (node (ref "R26") (pin "1") (pinfunction "1_1") (pintype "passive"))
      (node (ref "U2") (pin "13") (pinfunction "IN4-_13") (pintype "input"))
      (node (ref "VR9") (pin "2") (pinfunction "S_2") (pintype "passive"))
    )
    (net (code "44") (name "Net-(U2D-OUT4)") (class "Default")
      (node (ref "C5") (pin "2") (pinfunction "2_2") (pintype "passive"))
      (node (ref "J2") (pin "2") (pinfunction "2_2") (pintype "passive"))
      (node (ref "R26") (pin "2") (pinfunction "2_2") (pintype "passive"))
      (node (ref "U2") (pin "14") (pinfunction "OUT4_14") (pintype "output"))
    )
    (net (code "45") (name "Net-(U3A-OUT1)") (class "Default")
      (node (ref "R12") (pin "2") (pinfunction "2_2") (pintype "passive"))
      (node (ref "U3") (pin "1") (pinfunction "OUT1_1") (pintype "output"))
      (node (ref "VR5") (pin "3") (pinfunction "CW_3") (pintype "passive"))
    )
    (net (code "46") (name "Net-(U3B-OUT2)") (class "Default")
      (node (ref "R16") (pin "2") (pinfunction "2_2") (pintype "passive"))
      (node (ref "U3") (pin "7") (pinfunction "OUT2_7") (pintype "output"))
      (node (ref "VR6") (pin "3") (pinfunction "CW_3") (pintype "passive"))
    )
    (net (code "47") (name "unconnected-(U1B-GND-Pad11)") (class "Default")
      (node (ref "U1") (pin "11") (pinfunction "GND_11") (pintype "power_in+no_connect"))
    )
    (net (code "48") (name "unconnected-(U1B-V+-Pad4)") (class "Default")
      (node (ref "U1") (pin "4") (pinfunction "V+_4") (pintype "power_in+no_connect"))
    )
    (net (code "49") (name "unconnected-(U1C-GND-Pad11)") (class "Default")
      (node (ref "U1") (pin "11") (pinfunction "GND_11") (pintype "power_in+no_connect"))
    )
    (net (code "50") (name "unconnected-(U1C-V+-Pad4)") (class "Default")
      (node (ref "U1") (pin "4") (pinfunction "V+_4") (pintype "power_in+no_connect"))
    )
    (net (code "51") (name "unconnected-(U2B-GND-Pad11)") (class "Default")
      (node (ref "U2") (pin "11") (pinfunction "GND_11") (pintype "power_in+no_connect"))
    )
    (net (code "52") (name "unconnected-(U2B-V+-Pad4)") (class "Default")
      (node (ref "U2") (pin "4") (pinfunction "V+_4") (pintype "power_in+no_connect"))
    )
    (net (code "53") (name "unconnected-(U3A-GND-Pad11)") (class "Default")
      (node (ref "U3") (pin "11") (pinfunction "GND_11") (pintype "power_in+no_connect"))
    )
    (net (code "54") (name "unconnected-(U3A-V+-Pad4)") (class "Default")
      (node (ref "U3") (pin "4") (pinfunction "V+_4") (pintype "power_in+no_connect"))
    )
    (net (code "55") (name "unconnected-(U3C-GND-Pad11)") (class "Default")
      (node (ref "U3") (pin "11") (pinfunction "GND_11") (pintype "power_in+no_connect"))
    )
    (net (code "56") (name "unconnected-(U3C-V+-Pad4)") (class "Default")
      (node (ref "U3") (pin "4") (pinfunction "V+_4") (pintype "power_in+no_connect"))
    )
    (net (code "57") (name "unconnected-(VR2-CCW-Pad1)") (class "Default")
      (node (ref "VR2") (pin "1") (pinfunction "CCW_1") (pintype "passive"))
    )
    (net (code "58") (name "unconnected-(VR3-CCW-Pad1)") (class "Default")
      (node (ref "VR3") (pin "1") (pinfunction "CCW_1") (pintype "passive"))
    )
    (net (code "59") (name "unconnected-(VR4-CCW-Pad1)") (class "Default")
      (node (ref "VR4") (pin "1") (pinfunction "CCW_1") (pintype "passive"))
    )
    (net (code "60") (name "unconnected-(VR5-CCW-Pad1)") (class "Default")
      (node (ref "VR5") (pin "1") (pinfunction "CCW_1") (pintype "passive"))
    )
    (net (code "61") (name "unconnected-(VR6-CCW-Pad1)") (class "Default")
      (node (ref "VR6") (pin "1") (pinfunction "CCW_1") (pintype "passive"))
    )
    (net (code "62") (name "unconnected-(VR7-CCW-Pad1)") (class "Default")
      (node (ref "VR7") (pin "1") (pinfunction "CCW_1") (pintype "passive"))
    )
    (net (code "63") (name "unconnected-(VR9-CW-Pad3)") (class "Default")
      (node (ref "VR9") (pin "3") (pinfunction "CW_3") (pintype "passive"))
    )
  )
)
